# logicBlocks-Input.net
KiCad netlist of a schematic drawn in EAGLE
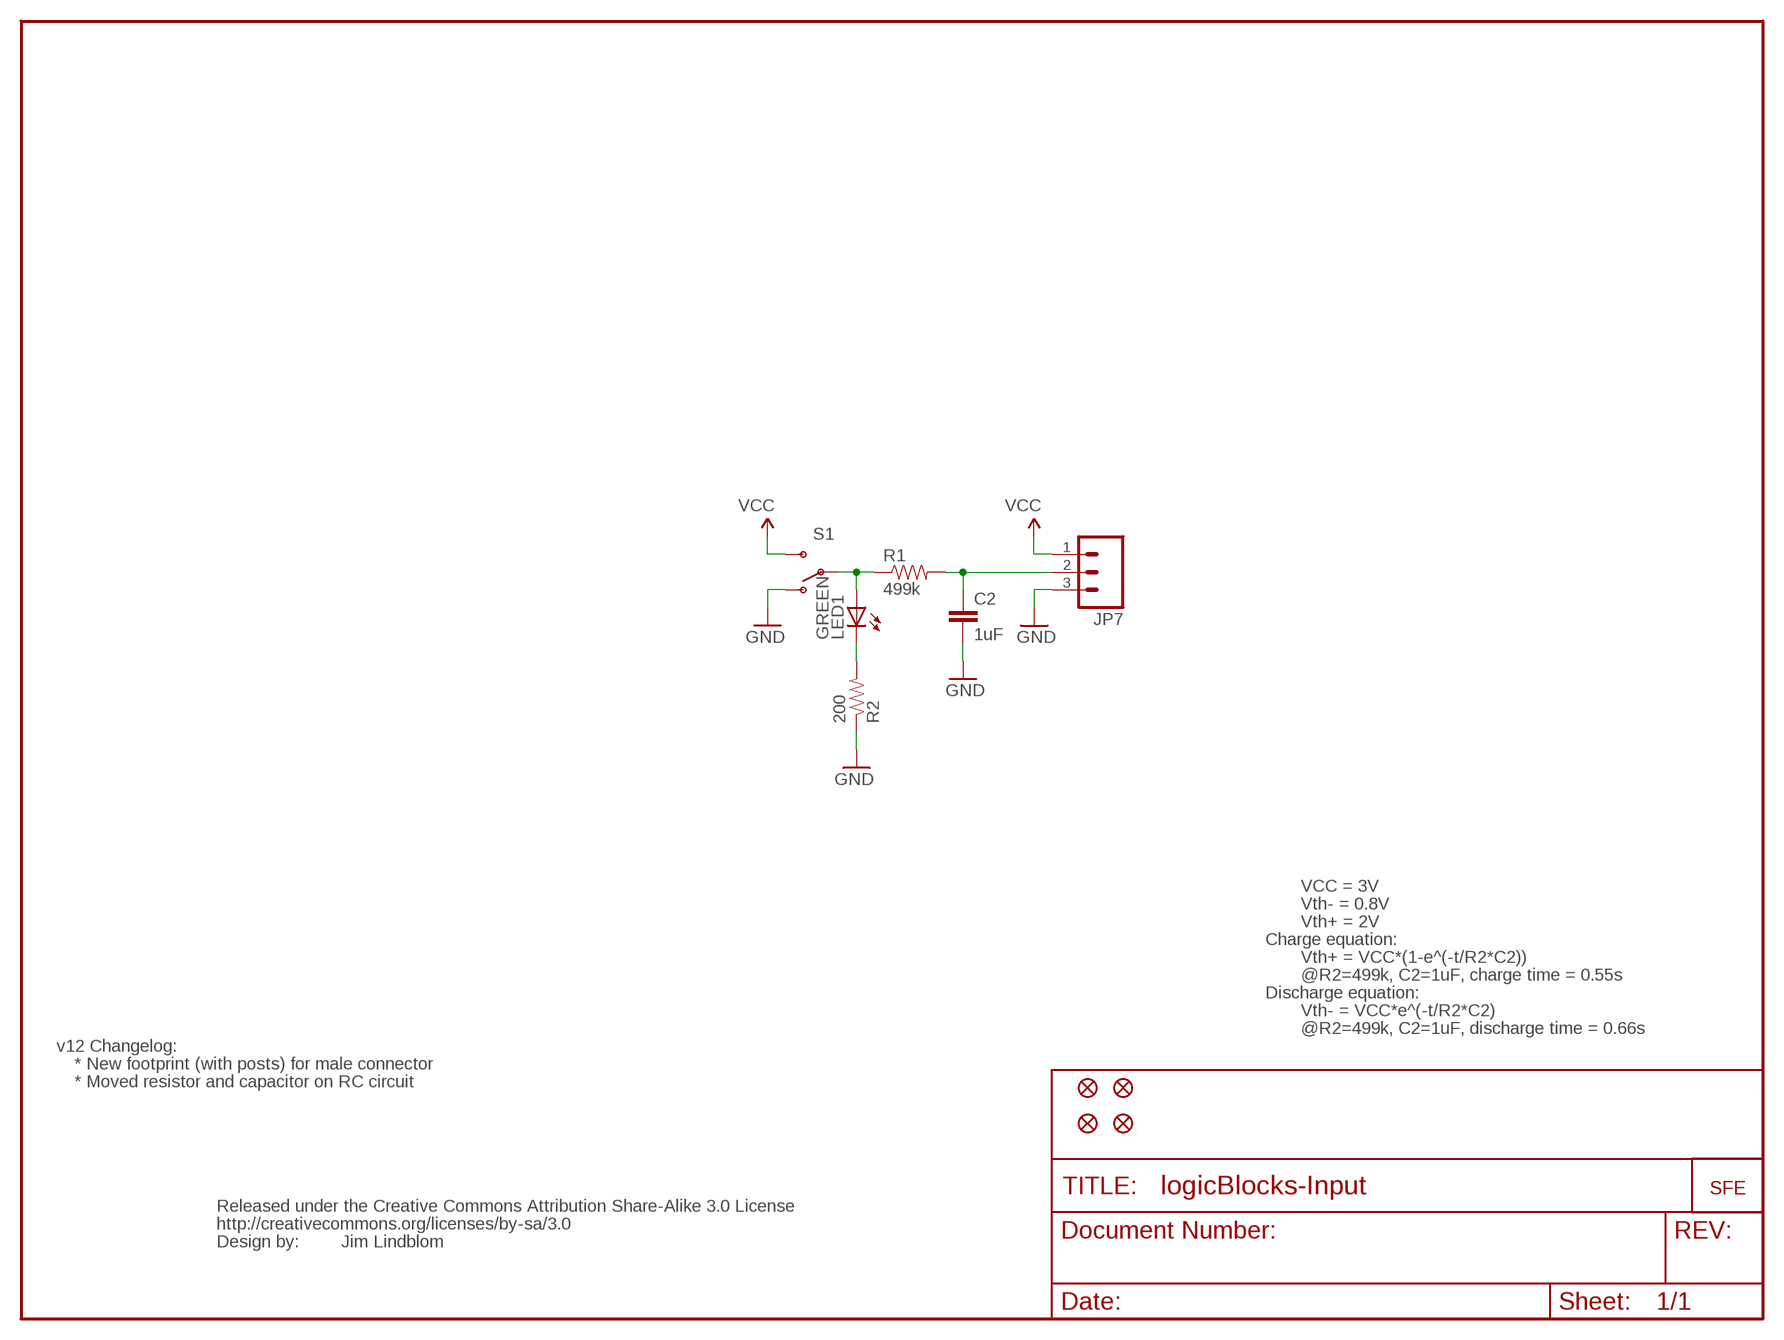
[diagram p0: schematic, sheet 1]

(export (version "E")
  (design (tool "Eeschema 10.0.6"))
  (components
    (comp (ref "C2")
      (value "1uF")
      (footprint "eagle-import:0402-CAP")
      (libsource (lib "eagle-import") (part "CAP0402-CAP"))
    )
    (comp (ref "JP2")
      (value "LOGO-SFESK")
      (footprint "eagle-import:SFE-LOGO-FLAME")
      (libsource (lib "eagle-import") (part "LOGO-SFESK"))
    )
    (comp (ref "JP3")
      (value "FIDUCIALUFIDUCIAL")
      (footprint "eagle-import:MICRO-FIDUCIAL")
      (libsource (lib "eagle-import") (part "FIDUCIALUFIDUCIAL"))
    )
    (comp (ref "JP4")
      (value "FIDUCIALUFIDUCIAL")
      (footprint "eagle-import:MICRO-FIDUCIAL")
      (libsource (lib "eagle-import") (part "FIDUCIALUFIDUCIAL"))
    )
    (comp (ref "JP5")
      (value "FIDUCIALUFIDUCIAL")
      (footprint "eagle-import:MICRO-FIDUCIAL")
      (libsource (lib "eagle-import") (part "FIDUCIALUFIDUCIAL"))
    )
    (comp (ref "JP6")
      (value "FIDUCIALUFIDUCIAL")
      (footprint "eagle-import:MICRO-FIDUCIAL")
      (libsource (lib "eagle-import") (part "FIDUCIALUFIDUCIAL"))
    )
    (comp (ref "JP7")
      (value "M03SMD_RA_MALE_POST")
      (footprint "eagle-import:1X03_SMD_RA_MALE_POST")
      (libsource (lib "eagle-import") (part "M03SMD_RA_MALE_POST"))
    )
    (comp (ref "LED1")
      (value "GREEN")
      (footprint "eagle-import:LED-1206")
      (libsource (lib "eagle-import") (part "LED1206"))
    )
    (comp (ref "R1")
      (value "499k")
      (footprint "eagle-import:0402-RES")
      (libsource (lib "eagle-import") (part "RESISTOR0402-RES"))
    )
    (comp (ref "R2")
      (value "200")
      (footprint "eagle-import:0402-RES")
      (libsource (lib "eagle-import") (part "RESISTOR0402-RES"))
    )
    (comp (ref "S1")
      (value "SWITCH-SPSTSMD")
      (footprint "eagle-import:AYZ0202")
      (libsource (lib "eagle-import") (part "SWITCH-SPSTSMD"))
    )
    (comp (ref "U$2")
      (value "CREATIVE_COMMONS")
      (footprint "eagle-import:CREATIVE_COMMONS")
      (libsource (lib "eagle-import") (part "CREATIVE_COMMONS"))
    )
  )
  (nets
    (net (code "1") (name "GND") (class "Default")
      (node (ref "C2") (pin "2") (pinfunction "2_2") (pintype "passive"))
      (node (ref "JP7") (pin "3") (pinfunction "3_3") (pintype "passive"))
      (node (ref "R2") (pin "1") (pinfunction "1_1") (pintype "passive"))
      (node (ref "S1") (pin "1") (pinfunction "O_1") (pintype "passive"))
    )
    (net (code "2") (name "Net-(C2-Pad1)") (class "Default")
      (node (ref "C2") (pin "1") (pinfunction "1_1") (pintype "passive"))
      (node (ref "JP7") (pin "2") (pinfunction "2_2") (pintype "passive"))
      (node (ref "R1") (pin "2") (pinfunction "2_2") (pintype "passive"))
    )
    (net (code "3") (name "Net-(LED1-PadC)") (class "Default")
      (node (ref "LED1") (pin "C") (pinfunction "C_C") (pintype "passive"))
      (node (ref "R2") (pin "2") (pinfunction "2_2") (pintype "passive"))
    )
    (net (code "4") (name "Net-(S1-P)") (class "Default")
      (node (ref "LED1") (pin "A") (pinfunction "A_A") (pintype "passive"))
      (node (ref "R1") (pin "1") (pinfunction "1_1") (pintype "passive"))
      (node (ref "S1") (pin "2") (pinfunction "P_2") (pintype "passive"))
    )
    (net (code "5") (name "VCC") (class "Default")
      (node (ref "JP7") (pin "1") (pinfunction "1_1") (pintype "passive"))
      (node (ref "S1") (pin "3") (pinfunction "S_3") (pintype "passive"))
    )
  )
)
